# LAUNCHXL-F28069_B_1400922_1.net
KiCad netlist of a schematic drawn in Altium Designer
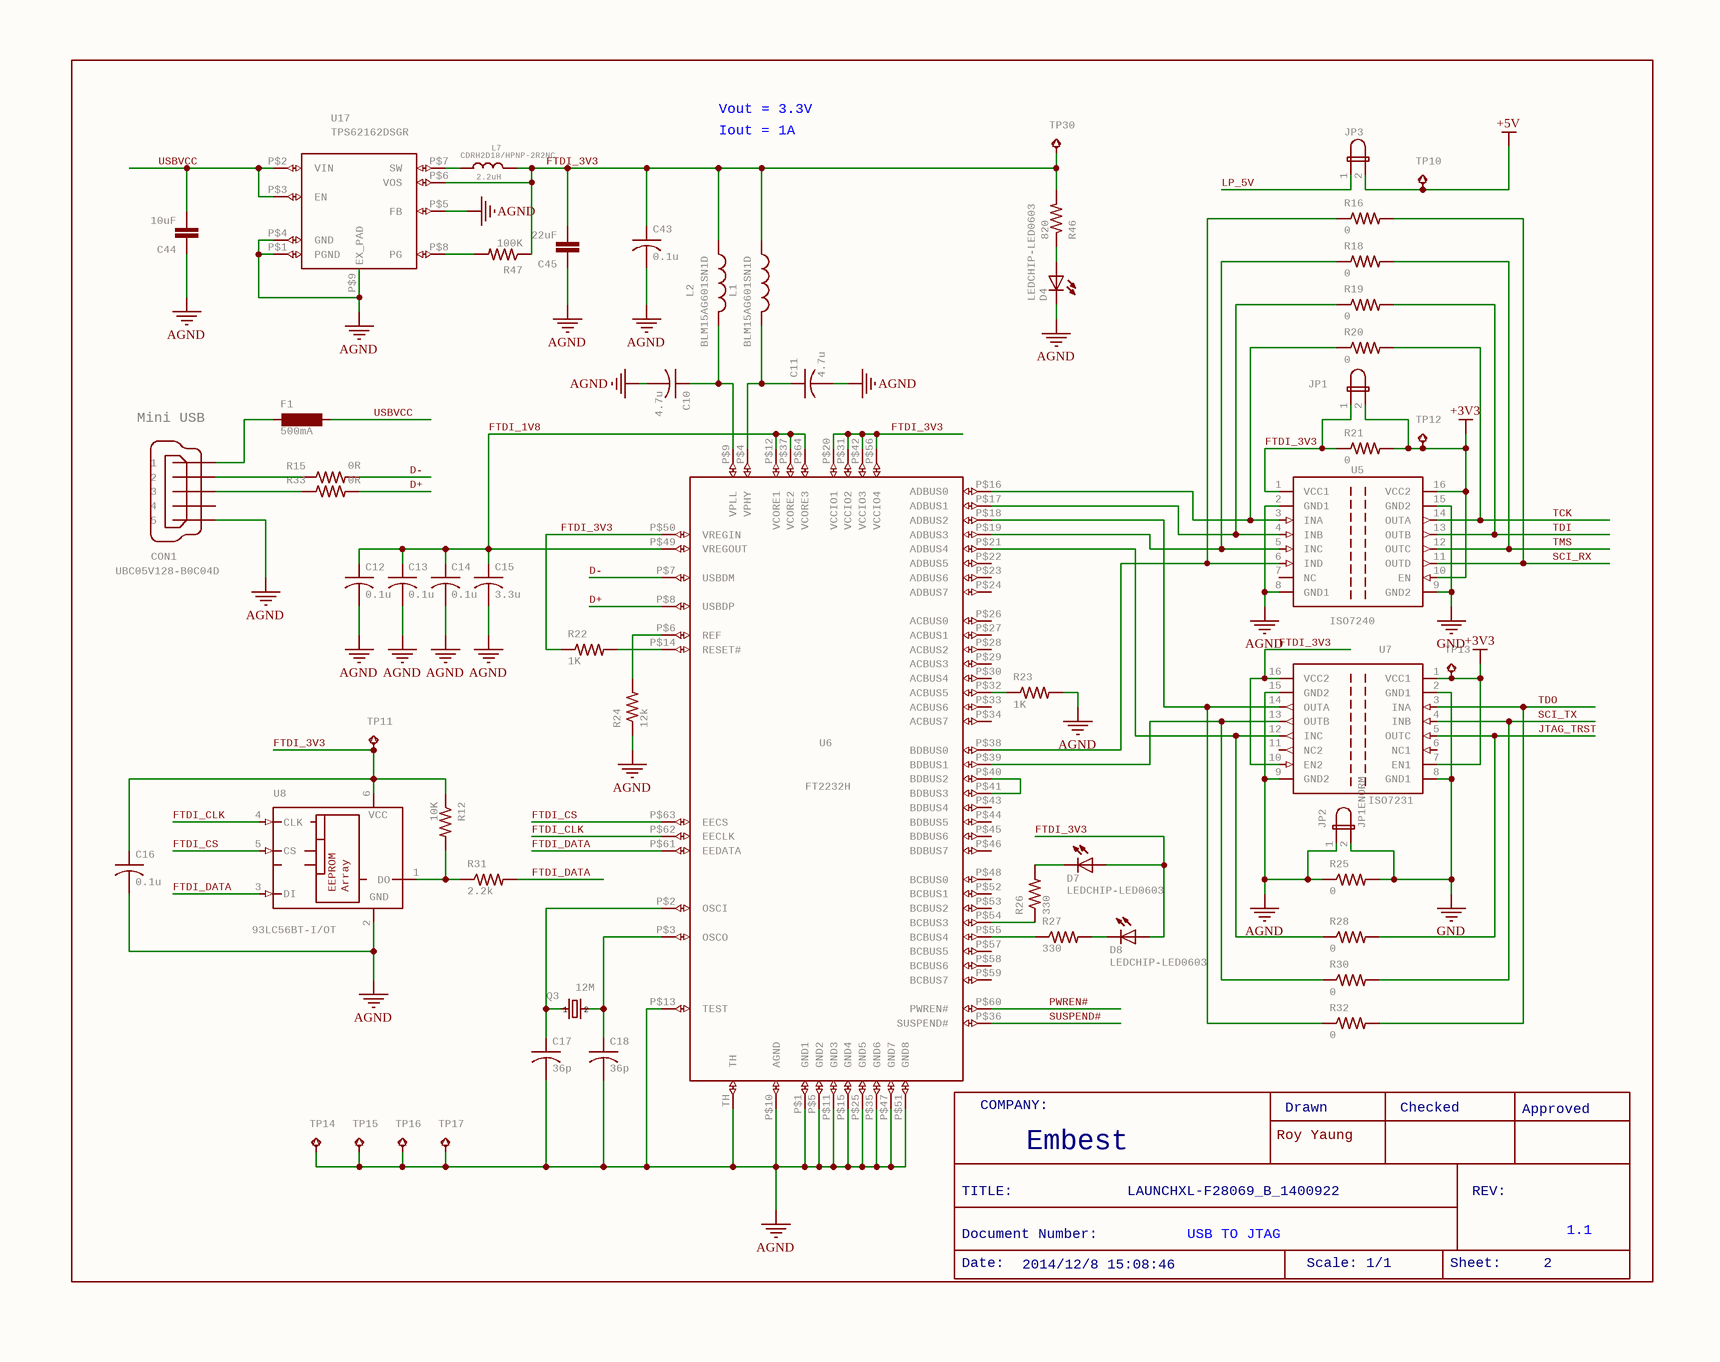
[diagram p0: LAUNCHXL-F28069_B_1400922_1.SchDoc]

(export (version "E")
  (design (tool "Eeschema 10.0.6"))
  (components
    (comp (ref "C10")
      (value "4.7u")
      (footprint "C0402")
      (description "CAPACITOR, American symbol")
      (libsource (lib "rcl") (part "C-USC0402"))
    )
    (comp (ref "C11")
      (value "4.7u")
      (footprint "C0402")
      (description "CAPACITOR, American symbol")
      (libsource (lib "rcl") (part "C-USC0402"))
    )
    (comp (ref "C12")
      (value "0.1u")
      (footprint "C0402")
      (description "CAPACITOR, American symbol")
      (libsource (lib "rcl") (part "C-USC0402"))
    )
    (comp (ref "C13")
      (value "0.1u")
      (footprint "C0402")
      (description "CAPACITOR, American symbol")
      (libsource (lib "rcl") (part "C-USC0402"))
    )
    (comp (ref "C14")
      (value "0.1u")
      (footprint "C0402")
      (description "CAPACITOR, American symbol")
      (libsource (lib "rcl") (part "C-USC0402"))
    )
    (comp (ref "C15")
      (value "3.3u")
      (footprint "C0402")
      (description "CAPACITOR, American symbol")
      (libsource (lib "rcl") (part "C-USC0402"))
    )
    (comp (ref "C16")
      (value "0.1u")
      (footprint "C0402")
      (description "CAPACITOR, American symbol")
      (libsource (lib "rcl") (part "C-USC0402"))
    )
    (comp (ref "C17")
      (value "36p")
      (footprint "C0402")
      (description "CAPACITOR, American symbol")
      (libsource (lib "rcl") (part "C-USC0402"))
    )
    (comp (ref "C18")
      (value "36p")
      (footprint "C0402")
      (description "CAPACITOR, American symbol")
      (libsource (lib "rcl") (part "C-USC0402"))
    )
    (comp (ref "C43")
      (value "0.1u")
      (footprint "C0402")
      (description "CAPACITOR, American symbol")
      (libsource (lib "rcl") (part "C-USC0402"))
    )
    (comp (ref "C44")
      (value "10uF")
      (footprint "SPARKFUN_1210")
      (description "CapacitorStandard 0603 ceramic capacitor, and 0.1\" leaded capacitor.")
      (fields (field (name "LIBRARYNAME") "RF430FRL152H_EVM_a"))
      (libsource (lib "RF430FRL152H_EVM_a") (part "SPARKFUN_CAP1210"))
    )
    (comp (ref "C45")
      (value "22uF")
      (footprint "SPARKFUN_1210")
      (description "CapacitorStandard 0603 ceramic capacitor, and 0.1\" leaded capacitor.")
      (fields (field (name "LIBRARYNAME") "RF430FRL152H_EVM_a"))
      (libsource (lib "RF430FRL152H_EVM_a") (part "SPARKFUN_CAP1210"))
    )
    (comp (ref "CON1")
      (value "UBC05V128-B0C04D")
      (footprint "32005-201")
      (description "MINI USB-B Conector   Source: www.cypressindustries.com")
      (fields (field (name "MF") "MF") (field (name "MPN") "MPN"))
      (libsource (lib "con-cypressindustries") (part "MINI-USB-32005-201"))
    )
    (comp (ref "D4")
      (value "LEDCHIP-LED0603")
      (footprint "CHIP-LED0603")
      (libsource (lib "led") (part "LEDCHIP-LED0603"))
    )
    (comp (ref "D7")
      (value "LEDCHIP-LED0603")
      (footprint "CHIP-LED0603")
      (libsource (lib "led") (part "LEDCHIP-LED0603"))
    )
    (comp (ref "D8")
      (value "LEDCHIP-LED0603")
      (footprint "CHIP-LED0603")
      (libsource (lib "led") (part "LEDCHIP-LED0603"))
    )
    (comp (ref "F1")
      (value "500mA")
      (footprint "L1812")
      (description "INDUCTOR, European symbol")
      (libsource (lib "rcl") (part "L-EUL1812"))
    )
    (comp (ref "JP1")
      (value "JP1ENORM")
      (footprint "JP1")
      (description "JUMPER")
      (libsource (lib "jumper") (part "JP1ENORM"))
    )
    (comp (ref "JP2")
      (value "JP1ENORM")
      (footprint "JP1")
      (description "JUMPER")
      (libsource (lib "jumper") (part "JP1ENORM"))
    )
    (comp (ref "JP3")
      (value "JP1ENORM")
      (footprint "JP1")
      (description "JUMPER")
      (libsource (lib "jumper") (part "JP1ENORM"))
    )
    (comp (ref "L1")
      (value "BLM15AG601SN1D")
      (footprint "R0402")
      (description "INDUCTOR, American symbol")
      (libsource (lib "rcl") (part "L-US0402"))
    )
    (comp (ref "L2")
      (value "BLM15AG601SN1D")
      (footprint "R0402")
      (description "INDUCTOR, American symbol")
      (libsource (lib "rcl") (part "L-US0402"))
    )
    (comp (ref "L7")
      (value "2.2uH")
      (footprint "INDUCT-3.2*3.2")
      (libsource (lib "LAUNCHXL-F28027") (part "VLF4012A`"))
    )
    (comp (ref "Q3")
      (value "12M")
      (footprint "HC49UP")
      (description "CRYSTAL")
      (fields
        (field (name "1") "1")
        (field (name "2") "2")
        (field (name "MF") "MF")
        (field (name "MPN") "MPN")
      )
      (libsource (lib "crystal") (part "CRYSTALHC49UP"))
    )
    (comp (ref "R12")
      (value "10K")
      (footprint "R0402")
      (description "RESISTOR, American symbol")
      (libsource (lib "rcl") (part "R-US_R0402"))
    )
    (comp (ref "R15")
      (value "0R")
      (footprint "R0402")
      (description "RESISTOR, American symbol")
      (libsource (lib "rcl") (part "R-US_R0402"))
    )
    (comp (ref "R16")
      (value "0")
      (footprint "R1206")
      (description "RESISTOR, American symbol")
      (libsource (lib "rcl") (part "R-US_R1206"))
    )
    (comp (ref "R18")
      (value "0")
      (footprint "R1206")
      (description "RESISTOR, American symbol")
      (libsource (lib "rcl") (part "R-US_R1206"))
    )
    (comp (ref "R19")
      (value "0")
      (footprint "R1206")
      (description "RESISTOR, American symbol")
      (libsource (lib "rcl") (part "R-US_R1206"))
    )
    (comp (ref "R20")
      (value "0")
      (footprint "R1206")
      (description "RESISTOR, American symbol")
      (libsource (lib "rcl") (part "R-US_R1206"))
    )
    (comp (ref "R21")
      (value "0")
      (footprint "R1206")
      (description "RESISTOR, American symbol")
      (libsource (lib "rcl") (part "R-US_R1206"))
    )
    (comp (ref "R22")
      (value "1K")
      (footprint "R0402")
      (description "RESISTOR, American symbol")
      (libsource (lib "rcl") (part "R-US_R0402"))
    )
    (comp (ref "R23")
      (value "1K")
      (footprint "R0402")
      (description "RESISTOR, American symbol")
      (libsource (lib "rcl") (part "R-US_R0402"))
    )
    (comp (ref "R24")
      (value "12k")
      (footprint "R0402")
      (description "RESISTOR, American symbol")
      (libsource (lib "rcl") (part "R-US_R0402"))
    )
    (comp (ref "R25")
      (value "0")
      (footprint "R1206")
      (description "RESISTOR, American symbol")
      (libsource (lib "rcl") (part "R-US_R1206"))
    )
    (comp (ref "R26")
      (value "330")
      (footprint "R0402")
      (description "RESISTOR, American symbol")
      (libsource (lib "rcl") (part "R-US_R0402"))
    )
    (comp (ref "R27")
      (value "330")
      (footprint "R0402")
      (description "RESISTOR, American symbol")
      (libsource (lib "rcl") (part "R-US_R0402"))
    )
    (comp (ref "R28")
      (value "0")
      (footprint "R1206")
      (description "RESISTOR, American symbol")
      (libsource (lib "rcl") (part "R-US_R1206"))
    )
    (comp (ref "R30")
      (value "0")
      (footprint "R1206")
      (description "RESISTOR, American symbol")
      (libsource (lib "rcl") (part "R-US_R1206"))
    )
    (comp (ref "R31")
      (value "2.2k")
      (footprint "R0402")
      (description "RESISTOR, American symbol")
      (libsource (lib "rcl") (part "R-US_R0402"))
    )
    (comp (ref "R32")
      (value "0")
      (footprint "R1206")
      (description "RESISTOR, American symbol")
      (libsource (lib "rcl") (part "R-US_R1206"))
    )
    (comp (ref "R33")
      (value "0R")
      (footprint "R0402")
      (description "RESISTOR, American symbol")
      (libsource (lib "rcl") (part "R-US_R0402"))
    )
    (comp (ref "R46")
      (value "820")
      (footprint "R0402")
      (description "RESISTOR, American symbol")
      (libsource (lib "rcl") (part "R-US_R0402"))
    )
    (comp (ref "R47")
      (value "100K")
      (footprint "R0402")
      (description "RESISTOR, American symbol")
      (libsource (lib "rcl") (part "R-US_R0402"))
    )
    (comp (ref "TP10")
      (value "TESTPAD_TPB1,27")
      (footprint "TESTPAD_B1,27")
      (description "Test pad")
      (fields (field (name "LIBRARYNAME") "RF430FRL152H_EVM_a"))
      (libsource (lib "RF430FRL152H_EVM_a") (part "TESTPAD_TPB1,27"))
    )
    (comp (ref "TP11")
      (value "TESTPAD_TPB1,27")
      (footprint "TESTPAD_B1,27")
      (description "Test pad")
      (fields (field (name "LIBRARYNAME") "RF430FRL152H_EVM_a"))
      (libsource (lib "RF430FRL152H_EVM_a") (part "TESTPAD_TPB1,27"))
    )
    (comp (ref "TP12")
      (value "TESTPAD_TPB1,27")
      (footprint "TESTPAD_B1,27")
      (description "Test pad")
      (fields (field (name "LIBRARYNAME") "RF430FRL152H_EVM_a"))
      (libsource (lib "RF430FRL152H_EVM_a") (part "TESTPAD_TPB1,27"))
    )
    (comp (ref "TP13")
      (value "TESTPAD_TPB1,27")
      (footprint "TESTPAD_B1,27")
      (description "Test pad")
      (fields (field (name "LIBRARYNAME") "RF430FRL152H_EVM_a"))
      (libsource (lib "RF430FRL152H_EVM_a") (part "TESTPAD_TPB1,27"))
    )
    (comp (ref "TP14")
      (value "TESTPAD_TPB1,27")
      (footprint "TESTPAD_B1,27")
      (description "Test pad")
      (fields (field (name "LIBRARYNAME") "RF430FRL152H_EVM_a"))
      (libsource (lib "RF430FRL152H_EVM_a") (part "TESTPAD_TPB1,27"))
    )
    (comp (ref "TP15")
      (value "TESTPAD_TPB1,27")
      (footprint "TESTPAD_B1,27")
      (description "Test pad")
      (fields (field (name "LIBRARYNAME") "RF430FRL152H_EVM_a"))
      (libsource (lib "RF430FRL152H_EVM_a") (part "TESTPAD_TPB1,27"))
    )
    (comp (ref "TP16")
      (value "TESTPAD_TPB1,27")
      (footprint "TESTPAD_B1,27")
      (description "Test pad")
      (fields (field (name "LIBRARYNAME") "RF430FRL152H_EVM_a"))
      (libsource (lib "RF430FRL152H_EVM_a") (part "TESTPAD_TPB1,27"))
    )
    (comp (ref "TP17")
      (value "TESTPAD_TPB1,27")
      (footprint "TESTPAD_B1,27")
      (description "Test pad")
      (fields (field (name "LIBRARYNAME") "RF430FRL152H_EVM_a"))
      (libsource (lib "RF430FRL152H_EVM_a") (part "TESTPAD_TPB1,27"))
    )
    (comp (ref "TP30")
      (value "TESTPAD_TPB1,27")
      (footprint "TESTPAD_B1,27")
      (description "Test pad")
      (fields (field (name "LIBRARYNAME") "RF430FRL152H_EVM_a"))
      (libsource (lib "RF430FRL152H_EVM_a") (part "TESTPAD_TPB1,27"))
    )
    (comp (ref "U$9")
      (value "ROY_JUMPER")
      (footprint "ROY_JUMPER")
      (libsource (lib "roy") (part "ROY_JUMPER"))
    )
    (comp (ref "U$10")
      (value "ROY_JUMPER")
      (footprint "ROY_JUMPER")
      (libsource (lib "roy") (part "ROY_JUMPER"))
    )
    (comp (ref "U$11")
      (value "ROY_JUMPER")
      (footprint "ROY_JUMPER")
      (libsource (lib "roy") (part "ROY_JUMPER"))
    )
    (comp (ref "U5")
      (value "ISO7240")
      (footprint "SO-16DW")
      (description "HIGH SPEED QUAD DIGITAL ISOLATORS   Source: http://focus.ti.com/lit/ds/symlink/iso7240m.pdf")
      (fields (field (name "MF") "MF") (field (name "MPN") "ISO7240MDW"))
      (libsource (lib "texas") (part "ISO7240"))
    )
    (comp (ref "U6")
      (value "FT2232H")
      (footprint "QFN64")
      (fields (field (name "LIBRARYNAME") "ti_trey"))
      (libsource (lib "ti_trey") (part "FT2232H"))
    )
    (comp (ref "U7") (value "ISO7231") (footprint "SO-16DW") (libsource (lib "texas") (part "ISO7231")))
    (comp (ref "U8")
      (value "93LC56BT-I/OT")
      (footprint "SOT23-6")
      (description "Serial EPROM   1 K/2 K/4 K, low voltage, Microwire")
      (fields
        (field (name "ARRAY") "Array")
        (field (name "VCC") "VCC")
        (field (name "GND") "GND")
        (field (name "EEPROM") "EEPROM")
        (field (name "LIBRARYNAME") "ti_trey")
      )
      (libsource (lib "ti_trey") (part "93*"))
    )
    (comp (ref "U17")
      (value "TPS62162DSGR")
      (footprint "TI_DSG8")
      (libsource (lib "LAUNCHXL-F28027") (part "TPS62162DSGR"))
    )
  )
  (nets
    (net (code "1") (name "+3V3") (class "Default")
      (node (ref "JP1") (pin "2") (pinfunction "2_2") (pintype "passive"))
      (node (ref "R21") (pin "2") (pinfunction "2_2") (pintype "passive"))
      (node (ref "TP12") (pin "TP") (pinfunction "TP_TP") (pintype "input"))
      (node (ref "TP13") (pin "TP") (pinfunction "TP_TP") (pintype "input"))
      (node (ref "U5") (pin "10") (pinfunction "EN_10") (pintype "input"))
      (node (ref "U5") (pin "16") (pinfunction "VCC2_16") (pintype "power_in"))
      (node (ref "U7") (pin "1") (pinfunction "VCC1_1") (pintype "power_in"))
      (node (ref "U7") (pin "7") (pinfunction "EN1_7") (pintype "passive"))
    )
    (net (code "2") (name "+5V") (class "Default")
      (node (ref "JP3") (pin "2") (pinfunction "2_2") (pintype "passive"))
      (node (ref "TP10") (pin "TP") (pinfunction "TP_TP") (pintype "input"))
    )
    (net (code "3") (name "/D+") (class "Default")
      (node (ref "R33") (pin "2") (pinfunction "2_2") (pintype "passive"))
      (node (ref "U6") (pin "P$8") (pinfunction "USBDP_P$8") (pintype "bidirectional"))
    )
    (net (code "4") (name "/D-") (class "Default")
      (node (ref "R15") (pin "2") (pinfunction "2_2") (pintype "passive"))
      (node (ref "U6") (pin "P$7") (pinfunction "USBDM_P$7") (pintype "bidirectional"))
    )
    (net (code "5") (name "/FTDI_1V8") (class "Default")
      (node (ref "C12") (pin "1") (pinfunction "1_1") (pintype "passive"))
      (node (ref "C13") (pin "1") (pinfunction "1_1") (pintype "passive"))
      (node (ref "C14") (pin "1") (pinfunction "1_1") (pintype "passive"))
      (node (ref "C15") (pin "1") (pinfunction "1_1") (pintype "passive"))
      (node (ref "U6") (pin "P$12") (pinfunction "VCORE1_P$12") (pintype "bidirectional"))
      (node (ref "U6") (pin "P$37") (pinfunction "VCORE2_P$37") (pintype "bidirectional"))
      (node (ref "U6") (pin "P$49") (pinfunction "VREGOUT_P$49") (pintype "bidirectional"))
      (node (ref "U6") (pin "P$64") (pinfunction "VCORE3_P$64") (pintype "bidirectional"))
    )
    (net (code "6") (name "/FTDI_3V3") (class "Default")
      (node (ref "C16") (pin "1") (pinfunction "1_1") (pintype "passive"))
      (node (ref "C43") (pin "1") (pinfunction "1_1") (pintype "passive"))
      (node (ref "C45") (pin "2") (pinfunction "2_2") (pintype "passive"))
      (node (ref "D7") (pin "A") (pinfunction "A_A") (pintype "passive"))
      (node (ref "D8") (pin "A") (pinfunction "A_A") (pintype "passive"))
      (node (ref "JP1") (pin "1") (pinfunction "1_1") (pintype "passive"))
      (node (ref "L1") (pin "1") (pinfunction "1_1") (pintype "passive"))
      (node (ref "L2") (pin "1") (pinfunction "1_1") (pintype "passive"))
      (node (ref "L7") (pin "P$1") (pinfunction "1_P$1") (pintype "bidirectional"))
      (node (ref "R12") (pin "1") (pinfunction "1_1") (pintype "passive"))
      (node (ref "R21") (pin "1") (pinfunction "1_1") (pintype "passive"))
      (node (ref "R22") (pin "1") (pinfunction "1_1") (pintype "passive"))
      (node (ref "R46") (pin "2") (pinfunction "2_2") (pintype "passive"))
      (node (ref "R47") (pin "1") (pinfunction "1_1") (pintype "passive"))
      (node (ref "TP11") (pin "TP") (pinfunction "TP_TP") (pintype "input"))
      (node (ref "TP30") (pin "TP") (pinfunction "TP_TP") (pintype "input"))
      (node (ref "U17") (pin "P$6") (pinfunction "VOS_P$6") (pintype "bidirectional"))
      (node (ref "U5") (pin "1") (pinfunction "VCC1_1") (pintype "power_in"))
      (node (ref "U6") (pin "P$20") (pinfunction "VCCIO1_P$20") (pintype "bidirectional"))
      (node (ref "U6") (pin "P$31") (pinfunction "VCCIO2_P$31") (pintype "bidirectional"))
      (node (ref "U6") (pin "P$42") (pinfunction "VCCIO3_P$42") (pintype "bidirectional"))
      (node (ref "U6") (pin "P$50") (pinfunction "VREGIN_P$50") (pintype "bidirectional"))
      (node (ref "U6") (pin "P$56") (pinfunction "VCCIO4_P$56") (pintype "bidirectional"))
      (node (ref "U7") (pin "10") (pinfunction "EN2_10") (pintype "input"))
      (node (ref "U7") (pin "16") (pinfunction "VCC2_16") (pintype "power_in"))
      (node (ref "U8") (pin "6") (pinfunction "VCC_6") (pintype "power_in"))
    )
    (net (code "7") (name "/FTDI_CLK") (class "Default")
      (node (ref "U6") (pin "P$62") (pinfunction "EECLK_P$62") (pintype "bidirectional"))
      (node (ref "U8") (pin "4") (pinfunction "CLK_4") (pintype "input"))
    )
    (net (code "8") (name "/FTDI_CS") (class "Default")
      (node (ref "U6") (pin "P$63") (pinfunction "EECS_P$63") (pintype "bidirectional"))
      (node (ref "U8") (pin "5") (pinfunction "CS_5") (pintype "input"))
    )
    (net (code "9") (name "/FTDI_DATA") (class "Default")
      (node (ref "R31") (pin "2") (pinfunction "2_2") (pintype "passive"))
      (node (ref "U6") (pin "P$61") (pinfunction "EEDATA_P$61") (pintype "bidirectional"))
      (node (ref "U8") (pin "3") (pinfunction "DI_3") (pintype "input"))
    )
    (net (code "10") (name "/JTAG_TRST") (class "Default")
      (node (ref "R28") (pin "2") (pinfunction "2_2") (pintype "passive"))
      (node (ref "U7") (pin "5") (pinfunction "OUTC_5") (pintype "input"))
    )
    (net (code "11") (name "/LP_5V") (class "Default")
      (node (ref "JP3") (pin "1") (pinfunction "1_1") (pintype "passive"))
    )
    (net (code "12") (name "/PWREN#") (class "Default")
      (node (ref "U6") (pin "P$60") (pinfunction "PWREN#_P$60") (pintype "bidirectional"))
    )
    (net (code "13") (name "/SCI_RX") (class "Default")
      (node (ref "R16") (pin "2") (pinfunction "2_2") (pintype "passive"))
      (node (ref "U5") (pin "11") (pinfunction "OUTD_11") (pintype "output"))
    )
    (net (code "14") (name "/SCI_TX") (class "Default")
      (node (ref "R30") (pin "2") (pinfunction "2_2") (pintype "passive"))
      (node (ref "U7") (pin "4") (pinfunction "INB_4") (pintype "input"))
    )
    (net (code "15") (name "/SUSPEND#") (class "Default")
      (node (ref "U6") (pin "P$36") (pinfunction "SUSPEND#_P$36") (pintype "bidirectional"))
    )
    (net (code "16") (name "/TCK") (class "Default")
      (node (ref "R20") (pin "2") (pinfunction "2_2") (pintype "passive"))
      (node (ref "U5") (pin "14") (pinfunction "OUTA_14") (pintype "output"))
    )
    (net (code "17") (name "/TDI") (class "Default")
      (node (ref "R19") (pin "2") (pinfunction "2_2") (pintype "passive"))
      (node (ref "U5") (pin "13") (pinfunction "OUTB_13") (pintype "output"))
    )
    (net (code "18") (name "/TDO") (class "Default")
      (node (ref "R32") (pin "2") (pinfunction "2_2") (pintype "passive"))
      (node (ref "U7") (pin "3") (pinfunction "INA_3") (pintype "input"))
    )
    (net (code "19") (name "/TMS") (class "Default")
      (node (ref "R18") (pin "2") (pinfunction "2_2") (pintype "passive"))
      (node (ref "U5") (pin "12") (pinfunction "OUTC_12") (pintype "output"))
    )
    (net (code "20") (name "/USBVCC") (class "Default")
      (node (ref "C44") (pin "2") (pinfunction "2_2") (pintype "passive"))
      (node (ref "F1") (pin "1") (pinfunction "1_1") (pintype "passive"))
      (node (ref "U17") (pin "P$2") (pinfunction "VIN_P$2") (pintype "bidirectional"))
      (node (ref "U17") (pin "P$3") (pinfunction "EN_P$3") (pintype "bidirectional"))
    )
    (net (code "21") (name "AGND") (class "Default")
      (node (ref "C10") (pin "2") (pinfunction "2_2") (pintype "passive"))
      (node (ref "C11") (pin "2") (pinfunction "2_2") (pintype "passive"))
      (node (ref "C12") (pin "2") (pinfunction "2_2") (pintype "passive"))
      (node (ref "C13") (pin "2") (pinfunction "2_2") (pintype "passive"))
      (node (ref "C14") (pin "2") (pinfunction "2_2") (pintype "passive"))
      (node (ref "C15") (pin "2") (pinfunction "2_2") (pintype "passive"))
      (node (ref "C16") (pin "2") (pinfunction "2_2") (pintype "passive"))
      (node (ref "C17") (pin "2") (pinfunction "2_2") (pintype "passive"))
      (node (ref "C18") (pin "2") (pinfunction "2_2") (pintype "passive"))
      (node (ref "C43") (pin "2") (pinfunction "2_2") (pintype "passive"))
      (node (ref "C44") (pin "1") (pinfunction "1_1") (pintype "passive"))
      (node (ref "C45") (pin "1") (pinfunction "1_1") (pintype "passive"))
      (node (ref "CON1") (pin "5") (pinfunction "5_5") (pintype "passive"))
      (node (ref "D4") (pin "C") (pinfunction "C_C") (pintype "passive"))
      (node (ref "JP2") (pin "1") (pinfunction "1_1") (pintype "passive"))
      (node (ref "R23") (pin "2") (pinfunction "2_2") (pintype "passive"))
      (node (ref "R24") (pin "1") (pinfunction "1_1") (pintype "passive"))
      (node (ref "R25") (pin "1") (pinfunction "1_1") (pintype "passive"))
      (node (ref "TP14") (pin "TP") (pinfunction "TP_TP") (pintype "input"))
      (node (ref "TP15") (pin "TP") (pinfunction "TP_TP") (pintype "input"))
      (node (ref "TP16") (pin "TP") (pinfunction "TP_TP") (pintype "input"))
      (node (ref "TP17") (pin "TP") (pinfunction "TP_TP") (pintype "input"))
      (node (ref "U17") (pin "P$1") (pinfunction "PGND_P$1") (pintype "bidirectional"))
      (node (ref "U17") (pin "P$4") (pinfunction "GND_P$4") (pintype "bidirectional"))
      (node (ref "U17") (pin "P$5") (pinfunction "FB_P$5") (pintype "bidirectional"))
      (node (ref "U17") (pin "P$9") (pinfunction "EX_PAD_P$9") (pintype "bidirectional"))
      (node (ref "U5") (pin "2") (pinfunction "GND1_2") (pintype "power_in"))
      (node (ref "U5") (pin "8") (pinfunction "GND1_8") (pintype "power_in"))
      (node (ref "U6") (pin "P$1") (pinfunction "GND1_P$1") (pintype "bidirectional"))
      (node (ref "U6") (pin "P$10") (pinfunction "AGND_P$10") (pintype "bidirectional"))
      (node (ref "U6") (pin "P$11") (pinfunction "GND3_P$11") (pintype "bidirectional"))
      (node (ref "U6") (pin "P$13") (pinfunction "TEST_P$13") (pintype "bidirectional"))
      (node (ref "U6") (pin "P$15") (pinfunction "GND4_P$15") (pintype "bidirectional"))
      (node (ref "U6") (pin "P$25") (pinfunction "GND5_P$25") (pintype "bidirectional"))
      (node (ref "U6") (pin "P$35") (pinfunction "GND6_P$35") (pintype "bidirectional"))
      (node (ref "U6") (pin "P$47") (pinfunction "GND7_P$47") (pintype "bidirectional"))
      (node (ref "U6") (pin "P$5") (pinfunction "GND2_P$5") (pintype "bidirectional"))
      (node (ref "U6") (pin "P$51") (pinfunction "GND8_P$51") (pintype "bidirectional"))
      (node (ref "U6") (pin "TH") (pinfunction "TH_TH") (pintype "bidirectional"))
      (node (ref "U7") (pin "15") (pinfunction "GND2_15") (pintype "power_in"))
      (node (ref "U7") (pin "9") (pinfunction "GND2_9") (pintype "power_in"))
      (node (ref "U8") (pin "2") (pinfunction "GND_2") (pintype "power_in"))
    )
    (net (code "22") (name "GND") (class "Default")
      (node (ref "JP2") (pin "2") (pinfunction "2_2") (pintype "passive"))
      (node (ref "R25") (pin "2") (pinfunction "2_2") (pintype "passive"))
      (node (ref "U5") (pin "15") (pinfunction "GND2_15") (pintype "power_in"))
      (node (ref "U5") (pin "9") (pinfunction "GND2_9") (pintype "power_in"))
      (node (ref "U7") (pin "2") (pinfunction "GND1_2") (pintype "power_in"))
      (node (ref "U7") (pin "8") (pinfunction "GND1_8") (pintype "power_in"))
    )
    (net (code "23") (name "Net-(CON1-Pad1)") (class "Default")
      (node (ref "CON1") (pin "1") (pinfunction "1_1") (pintype "passive"))
      (node (ref "F1") (pin "2") (pinfunction "2_2") (pintype "passive"))
    )
    (net (code "24") (name "Net-(CON1-Pad2)") (class "Default")
      (node (ref "CON1") (pin "2") (pinfunction "2_2") (pintype "passive"))
      (node (ref "R15") (pin "1") (pinfunction "1_1") (pintype "passive"))
    )
    (net (code "25") (name "Net-(CON1-Pad3)") (class "Default")
      (node (ref "CON1") (pin "3") (pinfunction "3_3") (pintype "passive"))
      (node (ref "R33") (pin "1") (pinfunction "1_1") (pintype "passive"))
    )
    (net (code "26") (name "Net-(D4-PadA)") (class "Default")
      (node (ref "D4") (pin "A") (pinfunction "A_A") (pintype "passive"))
      (node (ref "R46") (pin "1") (pinfunction "1_1") (pintype "passive"))
    )
    (net (code "27") (name "Net-(D7-PadC)") (class "Default")
      (node (ref "D7") (pin "C") (pinfunction "C_C") (pintype "passive"))
      (node (ref "R26") (pin "2") (pinfunction "2_2") (pintype "passive"))
    )
    (net (code "28") (name "Net-(D8-PadC)") (class "Default")
      (node (ref "D8") (pin "C") (pinfunction "C_C") (pintype "passive"))
      (node (ref "R27") (pin "2") (pinfunction "2_2") (pintype "passive"))
    )
    (net (code "29") (name "Net-(L7-2)") (class "Default")
      (node (ref "L7") (pin "P$2") (pinfunction "2_P$2") (pintype "bidirectional"))
      (node (ref "U17") (pin "P$7") (pinfunction "SW_P$7") (pintype "bidirectional"))
    )
    (net (code "30") (name "Net-(U5-INA)") (class "Default")
      (node (ref "R20") (pin "1") (pinfunction "1_1") (pintype "passive"))
      (node (ref "U5") (pin "3") (pinfunction "INA_3") (pintype "input"))
      (node (ref "U6") (pin "P$16") (pinfunction "ADBUS0_P$16") (pintype "bidirectional"))
    )
    (net (code "31") (name "Net-(U5-INB)") (class "Default")
      (node (ref "R19") (pin "1") (pinfunction "1_1") (pintype "passive"))
      (node (ref "U5") (pin "4") (pinfunction "INB_4") (pintype "input"))
      (node (ref "U6") (pin "P$17") (pinfunction "ADBUS1_P$17") (pintype "bidirectional"))
    )
    (net (code "32") (name "Net-(U5-INC)") (class "Default")
      (node (ref "R18") (pin "1") (pinfunction "1_1") (pintype "passive"))
      (node (ref "U5") (pin "5") (pinfunction "INC_5") (pintype "input"))
      (node (ref "U6") (pin "P$19") (pinfunction "ADBUS3_P$19") (pintype "bidirectional"))
    )
    (net (code "33") (name "Net-(U5-IND)") (class "Default")
      (node (ref "R16") (pin "1") (pinfunction "1_1") (pintype "passive"))
      (node (ref "U5") (pin "6") (pinfunction "IND_6") (pintype "input"))
      (node (ref "U6") (pin "P$38") (pinfunction "BDBUS0_P$38") (pintype "bidirectional"))
    )
    (net (code "34") (name "Net-(U6-ACBUS5)") (class "Default")
      (node (ref "R23") (pin "1") (pinfunction "1_1") (pintype "passive"))
      (node (ref "U6") (pin "P$32") (pinfunction "ACBUS5_P$32") (pintype "bidirectional"))
    )
    (net (code "35") (name "Net-(U6-ADBUS2)") (class "Default")
      (node (ref "R32") (pin "1") (pinfunction "1_1") (pintype "passive"))
      (node (ref "U6") (pin "P$18") (pinfunction "ADBUS2_P$18") (pintype "bidirectional"))
      (node (ref "U7") (pin "14") (pinfunction "OUTA_14") (pintype "output"))
    )
    (net (code "36") (name "Net-(U6-ADBUS4)") (class "Default")
      (node (ref "R28") (pin "1") (pinfunction "1_1") (pintype "passive"))
      (node (ref "U6") (pin "P$21") (pinfunction "ADBUS4_P$21") (pintype "bidirectional"))
      (node (ref "U7") (pin "12") (pinfunction "INC_12") (pintype "output"))
    )
    (net (code "37") (name "Net-(U6-BCBUS3)") (class "Default")
      (node (ref "R26") (pin "1") (pinfunction "1_1") (pintype "passive"))
      (node (ref "U6") (pin "P$54") (pinfunction "BCBUS3_P$54") (pintype "bidirectional"))
    )
    (net (code "38") (name "Net-(U6-BCBUS4)") (class "Default")
      (node (ref "R27") (pin "1") (pinfunction "1_1") (pintype "passive"))
      (node (ref "U6") (pin "P$55") (pinfunction "BCBUS4_P$55") (pintype "bidirectional"))
    )
    (net (code "39") (name "Net-(U6-BDBUS1)") (class "Default")
      (node (ref "R30") (pin "1") (pinfunction "1_1") (pintype "passive"))
      (node (ref "U6") (pin "P$39") (pinfunction "BDBUS1_P$39") (pintype "bidirectional"))
      (node (ref "U7") (pin "13") (pinfunction "OUTB_13") (pintype "output"))
    )
    (net (code "40") (name "Net-(U6-BDBUS2)") (class "Default")
      (node (ref "U6") (pin "P$40") (pinfunction "BDBUS2_P$40") (pintype "bidirectional"))
      (node (ref "U6") (pin "P$41") (pinfunction "BDBUS3_P$41") (pintype "bidirectional"))
    )
    (net (code "41") (name "Net-(U6-OSCI)") (class "Default")
      (node (ref "C17") (pin "1") (pinfunction "1_1") (pintype "passive"))
      (node (ref "Q3") (pin "1") (pinfunction "1_1") (pintype "passive"))
      (node (ref "U6") (pin "P$2") (pinfunction "OSCI_P$2") (pintype "bidirectional"))
    )
    (net (code "42") (name "Net-(U6-OSCO)") (class "Default")
      (node (ref "C18") (pin "1") (pinfunction "1_1") (pintype "passive"))
      (node (ref "Q3") (pin "2") (pinfunction "2_2") (pintype "passive"))
      (node (ref "U6") (pin "P$3") (pinfunction "OSCO_P$3") (pintype "bidirectional"))
    )
    (net (code "43") (name "Net-(U6-REF)") (class "Default")
      (node (ref "R24") (pin "2") (pinfunction "2_2") (pintype "passive"))
      (node (ref "U6") (pin "P$6") (pinfunction "REF_P$6") (pintype "bidirectional"))
    )
    (net (code "44") (name "Net-(U6-RESET#)") (class "Default")
      (node (ref "R22") (pin "2") (pinfunction "2_2") (pintype "passive"))
      (node (ref "U6") (pin "P$14") (pinfunction "RESET#_P$14") (pintype "bidirectional"))
    )
    (net (code "45") (name "Net-(U6-VPHY)") (class "Default")
      (node (ref "C11") (pin "1") (pinfunction "1_1") (pintype "passive"))
      (node (ref "L1") (pin "2") (pinfunction "2_2") (pintype "passive"))
      (node (ref "U6") (pin "P$4") (pinfunction "VPHY_P$4") (pintype "bidirectional"))
    )
    (net (code "46") (name "Net-(U6-VPLL)") (class "Default")
      (node (ref "C10") (pin "1") (pinfunction "1_1") (pintype "passive"))
      (node (ref "L2") (pin "2") (pinfunction "2_2") (pintype "passive"))
      (node (ref "U6") (pin "P$9") (pinfunction "VPLL_P$9") (pintype "bidirectional"))
    )
    (net (code "47") (name "Net-(U8-DO)") (class "Default")
      (node (ref "R12") (pin "2") (pinfunction "2_2") (pintype "passive"))
      (node (ref "R31") (pin "1") (pinfunction "1_1") (pintype "passive"))
      (node (ref "U8") (pin "1") (pinfunction "DO_1") (pintype "tri_state"))
    )
    (net (code "48") (name "Net-(U17-PG)") (class "Default")
      (node (ref "R47") (pin "2") (pinfunction "2_2") (pintype "passive"))
      (node (ref "U17") (pin "P$8") (pinfunction "PG_P$8") (pintype "bidirectional"))
    )
    (net (code "49") (name "unconnected-(CON1-Pad4)") (class "Default")
      (node (ref "CON1") (pin "4") (pinfunction "4_4") (pintype "passive"))
    )
    (net (code "50") (name "unconnected-(U5-NC-Pad7)") (class "Default")
      (node (ref "U5") (pin "7") (pinfunction "NC_7") (pintype "passive"))
    )
    (net (code "51") (name "unconnected-(U6-ACBUS0-PadP$26)") (class "Default")
      (node (ref "U6") (pin "P$26") (pinfunction "ACBUS0_P$26") (pintype "bidirectional"))
    )
    (net (code "52") (name "unconnected-(U6-ACBUS1-PadP$27)") (class "Default")
      (node (ref "U6") (pin "P$27") (pinfunction "ACBUS1_P$27") (pintype "bidirectional"))
    )
    (net (code "53") (name "unconnected-(U6-ACBUS2-PadP$28)") (class "Default")
      (node (ref "U6") (pin "P$28") (pinfunction "ACBUS2_P$28") (pintype "bidirectional"))
    )
    (net (code "54") (name "unconnected-(U6-ACBUS3-PadP$29)") (class "Default")
      (node (ref "U6") (pin "P$29") (pinfunction "ACBUS3_P$29") (pintype "bidirectional"))
    )
    (net (code "55") (name "unconnected-(U6-ACBUS4-PadP$30)") (class "Default")
      (node (ref "U6") (pin "P$30") (pinfunction "ACBUS4_P$30") (pintype "bidirectional"))
    )
    (net (code "56") (name "unconnected-(U6-ACBUS6-PadP$33)") (class "Default")
      (node (ref "U6") (pin "P$33") (pinfunction "ACBUS6_P$33") (pintype "bidirectional"))
    )
    (net (code "57") (name "unconnected-(U6-ACBUS7-PadP$34)") (class "Default")
      (node (ref "U6") (pin "P$34") (pinfunction "ACBUS7_P$34") (pintype "bidirectional"))
    )
    (net (code "58") (name "unconnected-(U6-ADBUS5-PadP$22)") (class "Default")
      (node (ref "U6") (pin "P$22") (pinfunction "ADBUS5_P$22") (pintype "bidirectional"))
    )
    (net (code "59") (name "unconnected-(U6-ADBUS6-PadP$23)") (class "Default")
      (node (ref "U6") (pin "P$23") (pinfunction "ADBUS6_P$23") (pintype "bidirectional"))
    )
    (net (code "60") (name "unconnected-(U6-ADBUS7-PadP$24)") (class "Default")
      (node (ref "U6") (pin "P$24") (pinfunction "ADBUS7_P$24") (pintype "bidirectional"))
    )
    (net (code "61") (name "unconnected-(U6-BCBUS0-PadP$48)") (class "Default")
      (node (ref "U6") (pin "P$48") (pinfunction "BCBUS0_P$48") (pintype "bidirectional"))
    )
    (net (code "62") (name "unconnected-(U6-BCBUS1-PadP$52)") (class "Default")
      (node (ref "U6") (pin "P$52") (pinfunction "BCBUS1_P$52") (pintype "bidirectional"))
    )
    (net (code "63") (name "unconnected-(U6-BCBUS2-PadP$53)") (class "Default")
      (node (ref "U6") (pin "P$53") (pinfunction "BCBUS2_P$53") (pintype "bidirectional"))
    )
    (net (code "64") (name "unconnected-(U6-BCBUS5-PadP$57)") (class "Default")
      (node (ref "U6") (pin "P$57") (pinfunction "BCBUS5_P$57") (pintype "bidirectional"))
    )
    (net (code "65") (name "unconnected-(U6-BCBUS6-PadP$58)") (class "Default")
      (node (ref "U6") (pin "P$58") (pinfunction "BCBUS6_P$58") (pintype "bidirectional"))
    )
    (net (code "66") (name "unconnected-(U6-BCBUS7-PadP$59)") (class "Default")
      (node (ref "U6") (pin "P$59") (pinfunction "BCBUS7_P$59") (pintype "bidirectional"))
    )
    (net (code "67") (name "unconnected-(U6-BDBUS4-PadP$43)") (class "Default")
      (node (ref "U6") (pin "P$43") (pinfunction "BDBUS4_P$43") (pintype "bidirectional"))
    )
    (net (code "68") (name "unconnected-(U6-BDBUS5-PadP$44)") (class "Default")
      (node (ref "U6") (pin "P$44") (pinfunction "BDBUS5_P$44") (pintype "bidirectional"))
    )
    (net (code "69") (name "unconnected-(U6-BDBUS6-PadP$45)") (class "Default")
      (node (ref "U6") (pin "P$45") (pinfunction "BDBUS6_P$45") (pintype "bidirectional"))
    )
    (net (code "70") (name "unconnected-(U6-BDBUS7-PadP$46)") (class "Default")
      (node (ref "U6") (pin "P$46") (pinfunction "BDBUS7_P$46") (pintype "bidirectional"))
    )
    (net (code "71") (name "unconnected-(U7-NC1-Pad6)") (class "Default")
      (node (ref "U7") (pin "6") (pinfunction "NC1_6") (pintype "input"))
    )
    (net (code "72") (name "unconnected-(U7-NC2-Pad11)") (class "Default")
      (node (ref "U7") (pin "11") (pinfunction "NC2_11") (pintype "output"))
    )
  )
)
